# node_prototype.net
KiCad netlist of a schematic drawn in EAGLE
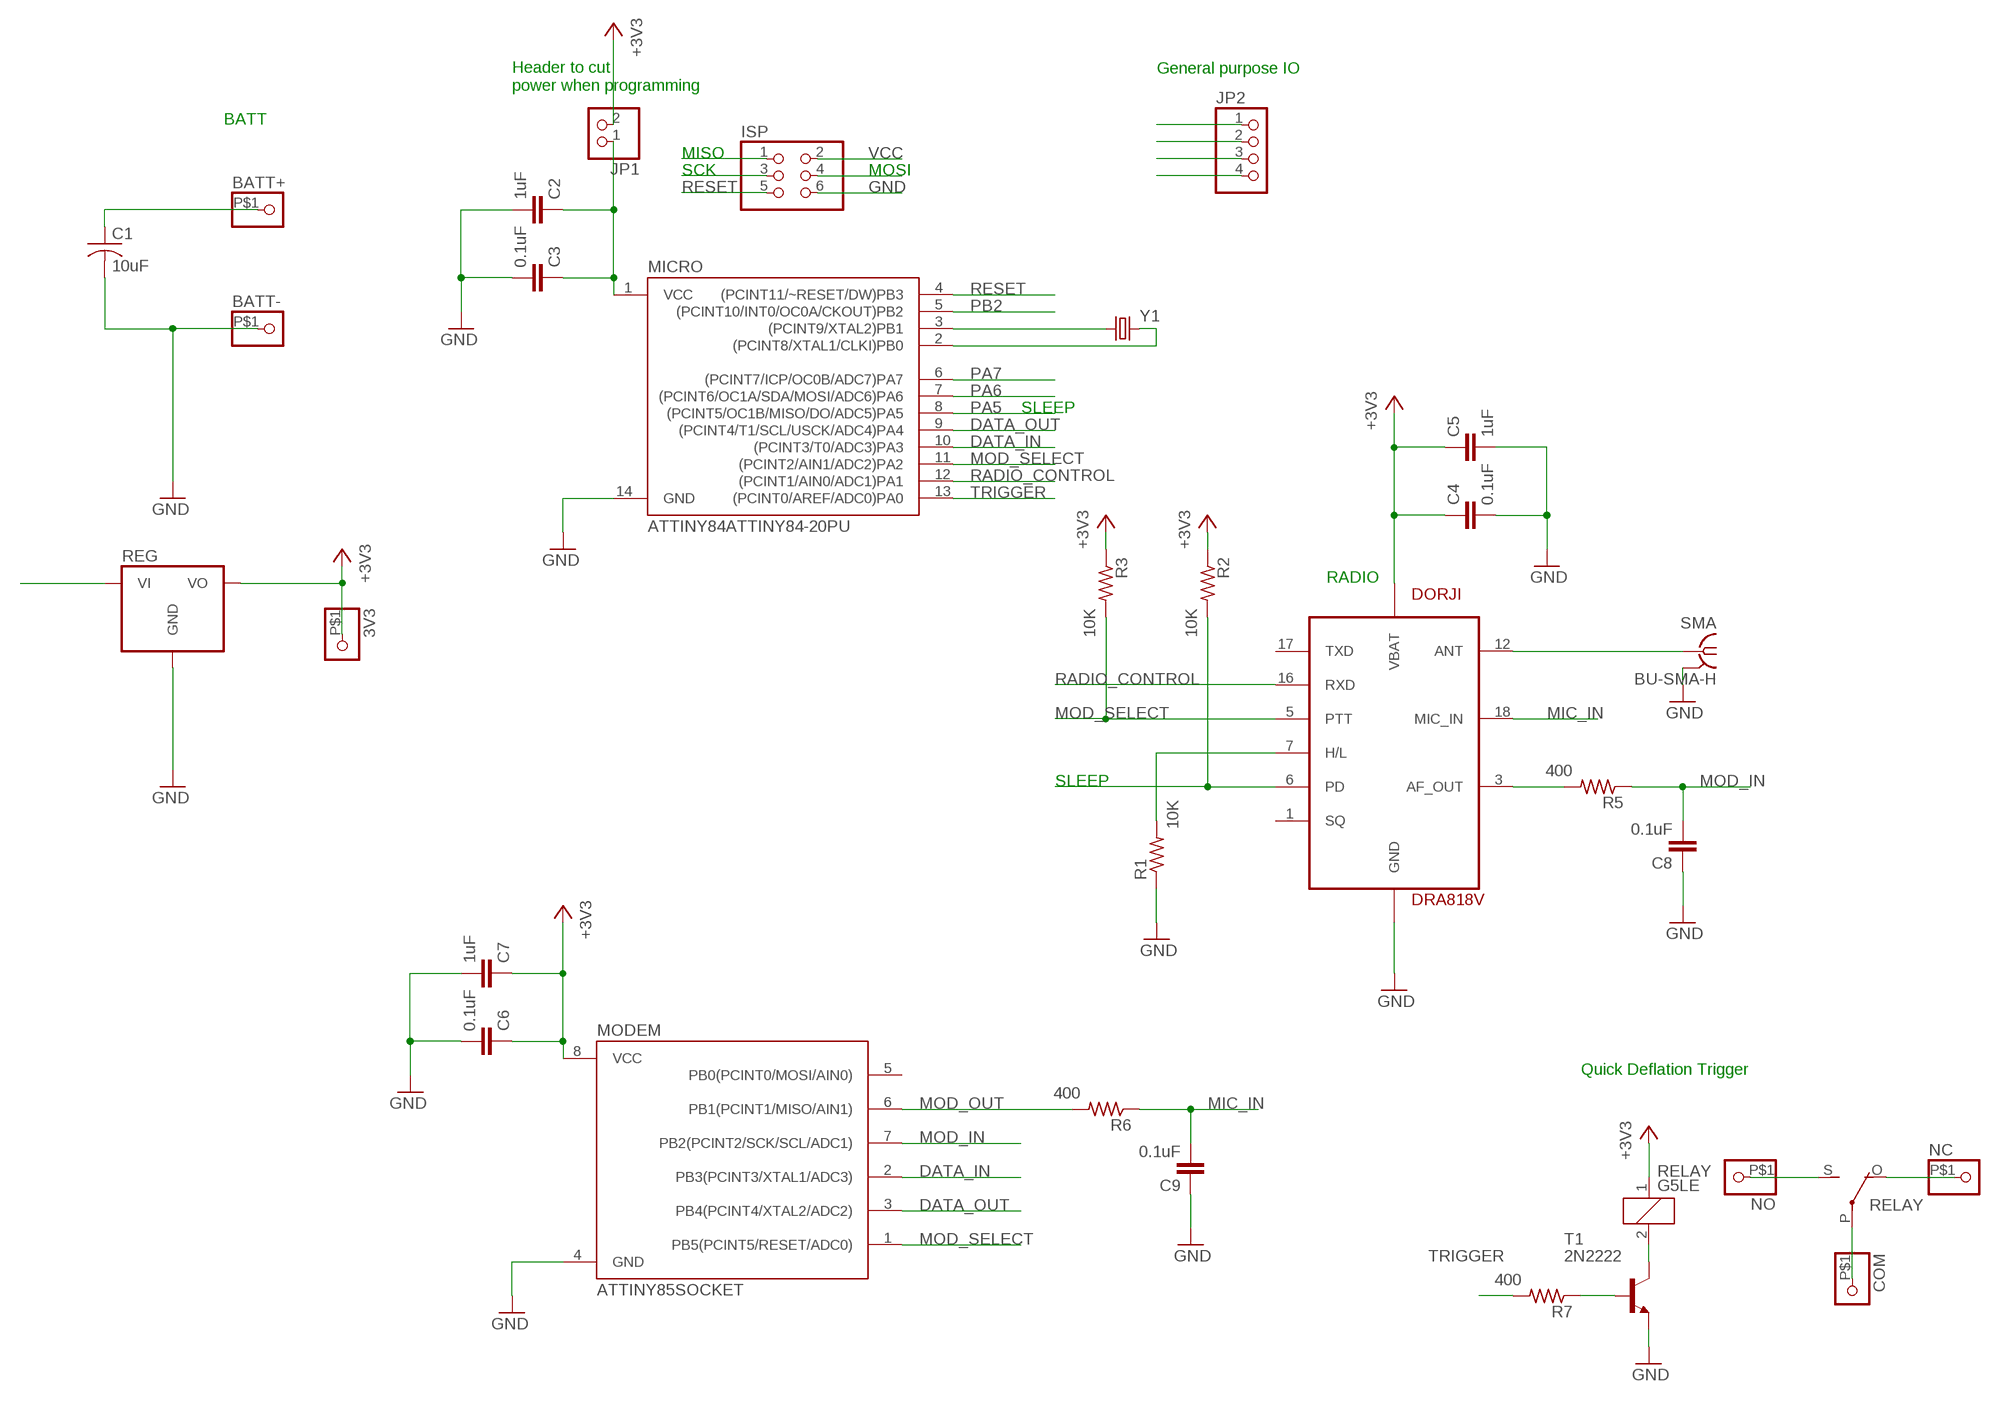
[diagram p0: schematic, sheet 1]

(export (version "E")
  (design (tool "Eeschema 10.0.6"))
  (components
    (comp (ref "3V3")
      (value "PINHD-1X1")
      (footprint "eagle-import:1X01")
      (libsource (lib "eagle-import") (part "PINHD-1X1"))
    )
    (comp (ref "BATT+")
      (value "PINHD-1X1")
      (footprint "eagle-import:1X01")
      (libsource (lib "eagle-import") (part "PINHD-1X1"))
    )
    (comp (ref "BATT-")
      (value "PINHD-1X1")
      (footprint "eagle-import:1X01")
      (libsource (lib "eagle-import") (part "PINHD-1X1"))
    )
    (comp (ref "C1")
      (value "10uF")
      (footprint "eagle-import:C025-050X050")
      (libsource (lib "eagle-import") (part "C-US025-050X050"))
    )
    (comp (ref "C2")
      (value "1uF")
      (footprint "eagle-import:C0603")
      (libsource (lib "eagle-import") (part "C-EUC0603"))
    )
    (comp (ref "C3")
      (value "0.1uF")
      (footprint "eagle-import:C0603")
      (libsource (lib "eagle-import") (part "C-EUC0603"))
    )
    (comp (ref "C4")
      (value "0.1uF")
      (footprint "eagle-import:C0603")
      (libsource (lib "eagle-import") (part "C-EUC0603"))
    )
    (comp (ref "C5")
      (value "1uF")
      (footprint "eagle-import:C0603")
      (libsource (lib "eagle-import") (part "C-EUC0603"))
    )
    (comp (ref "C6")
      (value "0.1uF")
      (footprint "eagle-import:C0603")
      (libsource (lib "eagle-import") (part "C-EUC0603"))
    )
    (comp (ref "C7")
      (value "1uF")
      (footprint "eagle-import:C0603")
      (libsource (lib "eagle-import") (part "C-EUC0603"))
    )
    (comp (ref "C8")
      (value "0.1uF")
      (footprint "eagle-import:C0603")
      (libsource (lib "eagle-import") (part "C-EUC0603"))
    )
    (comp (ref "C9")
      (value "0.1uF")
      (footprint "eagle-import:C0603")
      (libsource (lib "eagle-import") (part "C-EUC0603"))
    )
    (comp (ref "COM")
      (value "PINHD-1X1")
      (footprint "eagle-import:1X01")
      (libsource (lib "eagle-import") (part "PINHD-1X1"))
    )
    (comp (ref "DORJI")
      (value "DRA818V")
      (footprint "eagle-import:DORJI")
      (libsource (lib "eagle-import") (part "DORJIDRA818V"))
    )
    (comp (ref "ISP")
      (value "PINHD-2X3")
      (footprint "eagle-import:2X03")
      (libsource (lib "eagle-import") (part "PINHD-2X3"))
    )
    (comp (ref "JP1")
      (value "PINHD-1X2")
      (footprint "eagle-import:1X02")
      (libsource (lib "eagle-import") (part "PINHD-1X2"))
    )
    (comp (ref "JP2")
      (value "PINHD-1X4")
      (footprint "eagle-import:1X04")
      (libsource (lib "eagle-import") (part "PINHD-1X4"))
    )
    (comp (ref "MICRO")
      (value "ATTINY84ATTINY84-20PU")
      (footprint "eagle-import:DIL14")
      (libsource (lib "eagle-import") (part "ATTINY84ATTINY84-20PU"))
    )
    (comp (ref "MODEM")
      (value "ATTINY85SOCKET")
      (footprint "eagle-import:SOCKET-08")
      (libsource (lib "eagle-import") (part "ATTINY85SOCKET"))
    )
    (comp (ref "NC")
      (value "PINHD-1X1")
      (footprint "eagle-import:1X01")
      (libsource (lib "eagle-import") (part "PINHD-1X1"))
    )
    (comp (ref "NO")
      (value "PINHD-1X1")
      (footprint "eagle-import:1X01")
      (libsource (lib "eagle-import") (part "PINHD-1X1"))
    )
    (comp (ref "R1")
      (value "10K")
      (footprint "eagle-import:R0603")
      (libsource (lib "eagle-import") (part "R-US_R0603"))
    )
    (comp (ref "R2")
      (value "10K")
      (footprint "eagle-import:R0603")
      (libsource (lib "eagle-import") (part "R-US_R0603"))
    )
    (comp (ref "R3")
      (value "10K")
      (footprint "eagle-import:R0603")
      (libsource (lib "eagle-import") (part "R-US_R0603"))
    )
    (comp (ref "R5")
      (value "400")
      (footprint "eagle-import:R0603")
      (libsource (lib "eagle-import") (part "R-US_R0603"))
    )
    (comp (ref "R6")
      (value "400")
      (footprint "eagle-import:R0603")
      (libsource (lib "eagle-import") (part "R-US_R0603"))
    )
    (comp (ref "R7")
      (value "400")
      (footprint "eagle-import:R0603")
      (libsource (lib "eagle-import") (part "R-US_R0603"))
    )
    (comp (ref "REG")
      (value "AP1117-3.3SOT223")
      (footprint "eagle-import:SOT223")
      (libsource (lib "eagle-import") (part "AP1117-3.3SOT223"))
    )
    (comp (ref "RELAY")
      (value "G5LE")
      (footprint "eagle-import:G5LE")
      (libsource (lib "eagle-import") (part "G5LE"))
    )
    (comp (ref "SMA")
      (value "BU-SMA-H")
      (footprint "eagle-import:BU-SMA-H")
      (libsource (lib "eagle-import") (part "BU-SMA-H"))
    )
    (comp (ref "T1")
      (value "2N2222")
      (footprint "eagle-import:TO18")
      (libsource (lib "eagle-import") (part "2N2222"))
    )
    (comp (ref "Y1")
      (value "CRYSTAL")
      (footprint "eagle-import:MYSMD2_RESONATOR")
      (libsource (lib "eagle-import") (part "CRYSTAL"))
    )
  )
  (nets
    (net (code "1") (name "+3V3") (class "Default")
      (node (ref "3V3") (pin "P$1") (pinfunction "1_P$1") (pintype "passive"))
      (node (ref "C4") (pin "1") (pinfunction "1_1") (pintype "passive"))
      (node (ref "C5") (pin "1") (pinfunction "1_1") (pintype "passive"))
      (node (ref "C6") (pin "1") (pinfunction "1_1") (pintype "passive"))
      (node (ref "C7") (pin "1") (pinfunction "1_1") (pintype "passive"))
      (node (ref "DORJI") (pin "8") (pinfunction "VBAT_8") (pintype "bidirectional"))
      (node (ref "JP1") (pin "2") (pinfunction "2_2") (pintype "passive"))
      (node (ref "MODEM") (pin "8") (pinfunction "VCC_8") (pintype "bidirectional"))
      (node (ref "R2") (pin "1") (pinfunction "1_1") (pintype "passive"))
      (node (ref "R3") (pin "1") (pinfunction "1_1") (pintype "passive"))
      (node (ref "REG") (pin "2") (pinfunction "VO_2") (pintype "passive"))
      (node (ref "REG") (pin "4") (pinfunction "VO_4") (pintype "passive"))
      (node (ref "RELAY") (pin "1") (pinfunction "1_1") (pintype "passive"))
    )
    (net (code "2") (name "/BATT") (class "Default")
      (node (ref "BATT+") (pin "P$1") (pinfunction "1_P$1") (pintype "passive"))
      (node (ref "C1") (pin "1") (pinfunction "1_1") (pintype "passive"))
      (node (ref "REG") (pin "3") (pinfunction "VI_3") (pintype "input"))
    )
    (net (code "3") (name "/DATA_IN") (class "Default")
      (node (ref "MICRO") (pin "10") (pinfunction "(PCINT3/T0/ADC3)PA3_10") (pintype "bidirectional"))
      (node (ref "MODEM") (pin "2") (pinfunction "PB3(PCINT3/XTAL1/ADC3)_2") (pintype "bidirectional"))
    )
    (net (code "4") (name "/DATA_OUT") (class "Default")
      (node (ref "ISP") (pin "3") (pinfunction "3_3") (pintype "passive"))
      (node (ref "MICRO") (pin "9") (pinfunction "(PCINT4/T1/SCL/USCK/ADC4)PA4_9") (pintype "bidirectional"))
      (node (ref "MODEM") (pin "3") (pinfunction "PB4(PCINT4/XTAL2/ADC2)_3") (pintype "bidirectional"))
    )
    (net (code "5") (name "/MIC_IN") (class "Default")
      (node (ref "C9") (pin "2") (pinfunction "2_2") (pintype "passive"))
      (node (ref "DORJI") (pin "18") (pinfunction "MIC_IN_18") (pintype "bidirectional"))
      (node (ref "R6") (pin "1") (pinfunction "1_1") (pintype "passive"))
    )
    (net (code "6") (name "/MOD_IN") (class "Default")
      (node (ref "C8") (pin "2") (pinfunction "2_2") (pintype "passive"))
      (node (ref "MODEM") (pin "7") (pinfunction "PB2(PCINT2/SCK/SCL/ADC1)_7") (pintype "bidirectional"))
      (node (ref "R5") (pin "1") (pinfunction "1_1") (pintype "passive"))
    )
    (net (code "7") (name "/MOD_OUT") (class "Default")
      (node (ref "MODEM") (pin "6") (pinfunction "PB1(PCINT1/MISO/AIN1)_6") (pintype "bidirectional"))
      (node (ref "R6") (pin "2") (pinfunction "2_2") (pintype "passive"))
    )
    (net (code "8") (name "/MOD_SELECT") (class "Default")
      (node (ref "DORJI") (pin "5") (pinfunction "PTT_5") (pintype "bidirectional"))
      (node (ref "MICRO") (pin "11") (pinfunction "(PCINT2/AIN1/ADC2)PA2_11") (pintype "bidirectional"))
      (node (ref "MODEM") (pin "1") (pinfunction "PB5(PCINT5/RESET/ADC0)_1") (pintype "bidirectional"))
      (node (ref "R3") (pin "2") (pinfunction "2_2") (pintype "passive"))
    )
    (net (code "9") (name "/PA5") (class "Default")
      (node (ref "DORJI") (pin "6") (pinfunction "PD_6") (pintype "bidirectional"))
      (node (ref "ISP") (pin "1") (pinfunction "1_1") (pintype "passive"))
      (node (ref "JP2") (pin "4") (pinfunction "4_4") (pintype "passive"))
      (node (ref "MICRO") (pin "8") (pinfunction "(PCINT5/OC1B/MISO/DO/ADC5)PA5_8") (pintype "bidirectional"))
      (node (ref "R2") (pin "2") (pinfunction "2_2") (pintype "passive"))
    )
    (net (code "10") (name "/PA6") (class "Default")
      (node (ref "ISP") (pin "4") (pinfunction "4_4") (pintype "passive"))
      (node (ref "JP2") (pin "3") (pinfunction "3_3") (pintype "passive"))
      (node (ref "MICRO") (pin "7") (pinfunction "(PCINT6/OC1A/SDA/MOSI/ADC6)PA6_7") (pintype "bidirectional"))
    )
    (net (code "11") (name "/PA7") (class "Default")
      (node (ref "JP2") (pin "2") (pinfunction "2_2") (pintype "passive"))
      (node (ref "MICRO") (pin "6") (pinfunction "(PCINT7/ICP/OC0B/ADC7)PA7_6") (pintype "bidirectional"))
    )
    (net (code "12") (name "/PB2") (class "Default")
      (node (ref "JP2") (pin "1") (pinfunction "1_1") (pintype "passive"))
      (node (ref "MICRO") (pin "5") (pinfunction "(PCINT10/INT0/OC0A/CKOUT)PB2_5") (pintype "bidirectional"))
    )
    (net (code "13") (name "/RADIO_CONTROL") (class "Default")
      (node (ref "DORJI") (pin "16") (pinfunction "RXD_16") (pintype "bidirectional"))
      (node (ref "MICRO") (pin "12") (pinfunction "(PCINT1/AIN0/ADC1)PA1_12") (pintype "bidirectional"))
    )
    (net (code "14") (name "/RESET") (class "Default")
      (node (ref "ISP") (pin "5") (pinfunction "5_5") (pintype "passive"))
      (node (ref "MICRO") (pin "4") (pinfunction "(PCINT11/~{RESET/DW})PB3_4") (pintype "bidirectional"))
    )
    (net (code "15") (name "/TRIGGER") (class "Default")
      (node (ref "MICRO") (pin "13") (pinfunction "(PCINT0/AREF/ADC0)PA0_13") (pintype "bidirectional"))
      (node (ref "R7") (pin "2") (pinfunction "2_2") (pintype "passive"))
    )
    (net (code "16") (name "/VCC") (class "Default")
      (node (ref "C2") (pin "1") (pinfunction "1_1") (pintype "passive"))
      (node (ref "C3") (pin "1") (pinfunction "1_1") (pintype "passive"))
      (node (ref "ISP") (pin "2") (pinfunction "2_2") (pintype "passive"))
      (node (ref "JP1") (pin "1") (pinfunction "1_1") (pintype "passive"))
      (node (ref "MICRO") (pin "1") (pinfunction "VCC_1") (pintype "bidirectional"))
    )
    (net (code "17") (name "GND") (class "Default")
      (node (ref "BATT-") (pin "P$1") (pinfunction "1_P$1") (pintype "passive"))
      (node (ref "C1") (pin "2") (pinfunction "2_2") (pintype "passive"))
      (node (ref "C2") (pin "2") (pinfunction "2_2") (pintype "passive"))
      (node (ref "C3") (pin "2") (pinfunction "2_2") (pintype "passive"))
      (node (ref "C4") (pin "2") (pinfunction "2_2") (pintype "passive"))
      (node (ref "C5") (pin "2") (pinfunction "2_2") (pintype "passive"))
      (node (ref "C6") (pin "2") (pinfunction "2_2") (pintype "passive"))
      (node (ref "C7") (pin "2") (pinfunction "2_2") (pintype "passive"))
      (node (ref "C8") (pin "1") (pinfunction "1_1") (pintype "passive"))
      (node (ref "C9") (pin "1") (pinfunction "1_1") (pintype "passive"))
      (node (ref "DORJI") (pin "10") (pinfunction "GND_10") (pintype "bidirectional"))
      (node (ref "DORJI") (pin "9") (pinfunction "GND_9") (pintype "bidirectional"))
      (node (ref "ISP") (pin "6") (pinfunction "6_6") (pintype "passive"))
      (node (ref "MICRO") (pin "14") (pinfunction "GND_14") (pintype "bidirectional"))
      (node (ref "MODEM") (pin "4") (pinfunction "GND_4") (pintype "bidirectional"))
      (node (ref "R1") (pin "1") (pinfunction "1_1") (pintype "passive"))
      (node (ref "REG") (pin "1") (pinfunction "GND_1") (pintype "input"))
      (node (ref "SMA") (pin "2") (pinfunction "2_2") (pintype "passive"))
      (node (ref "SMA") (pin "3") (pinfunction "2_3") (pintype "passive"))
      (node (ref "SMA") (pin "4") (pinfunction "2_4") (pintype "passive"))
      (node (ref "SMA") (pin "5") (pinfunction "2_5") (pintype "passive"))
      (node (ref "T1") (pin "1") (pinfunction "E_1") (pintype "passive"))
    )
    (net (code "18") (name "Net-(COM-1)") (class "Default")
      (node (ref "COM") (pin "P$1") (pinfunction "1_P$1") (pintype "passive"))
      (node (ref "RELAY") (pin "P") (pinfunction "P_P") (pintype "passive"))
    )
    (net (code "19") (name "Net-(DORJI-AF_OUT)") (class "Default")
      (node (ref "DORJI") (pin "3") (pinfunction "AF_OUT_3") (pintype "bidirectional"))
      (node (ref "R5") (pin "2") (pinfunction "2_2") (pintype "passive"))
    )
    (net (code "20") (name "Net-(DORJI-ANT)") (class "Default")
      (node (ref "DORJI") (pin "12") (pinfunction "ANT_12") (pintype "bidirectional"))
      (node (ref "SMA") (pin "1") (pinfunction "1_1") (pintype "passive"))
    )
    (net (code "21") (name "Net-(DORJI-H{slash}L)") (class "Default")
      (node (ref "DORJI") (pin "7") (pinfunction "H/L_7") (pintype "bidirectional"))
      (node (ref "R1") (pin "2") (pinfunction "2_2") (pintype "passive"))
    )
    (net (code "22") (name "Net-(MICRO-(PCINT8{slash}XTAL1{slash}CLKI)PB0)") (class "Default")
      (node (ref "MICRO") (pin "2") (pinfunction "(PCINT8/XTAL1/CLKI)PB0_2") (pintype "bidirectional"))
      (node (ref "Y1") (pin "3") (pinfunction "2_3") (pintype "passive"))
    )
    (net (code "23") (name "Net-(MICRO-(PCINT9{slash}XTAL2)PB1)") (class "Default")
      (node (ref "MICRO") (pin "3") (pinfunction "(PCINT9/XTAL2)PB1_3") (pintype "bidirectional"))
      (node (ref "Y1") (pin "1") (pinfunction "1_1") (pintype "passive"))
    )
    (net (code "24") (name "Net-(NC-1)") (class "Default")
      (node (ref "NC") (pin "P$1") (pinfunction "1_P$1") (pintype "passive"))
      (node (ref "RELAY") (pin "O") (pinfunction "O_O") (pintype "passive"))
    )
    (net (code "25") (name "Net-(NO-1)") (class "Default")
      (node (ref "NO") (pin "P$1") (pinfunction "1_P$1") (pintype "passive"))
      (node (ref "RELAY") (pin "S") (pinfunction "S_S") (pintype "passive"))
    )
    (net (code "26") (name "Net-(T1-B)") (class "Default")
      (node (ref "R7") (pin "1") (pinfunction "1_1") (pintype "passive"))
      (node (ref "T1") (pin "2") (pinfunction "B_2") (pintype "passive"))
    )
    (net (code "27") (name "Net-(T1-C)") (class "Default")
      (node (ref "RELAY") (pin "2") (pinfunction "2_2") (pintype "passive"))
      (node (ref "T1") (pin "3") (pinfunction "C_3") (pintype "passive"))
    )
    (net (code "28") (name "unconnected-(DORJI-SQ-Pad1)") (class "Default")
      (node (ref "DORJI") (pin "1") (pinfunction "SQ_1") (pintype "bidirectional"))
    )
    (net (code "29") (name "unconnected-(DORJI-TXD-Pad17)") (class "Default")
      (node (ref "DORJI") (pin "17") (pinfunction "TXD_17") (pintype "bidirectional"))
    )
    (net (code "30") (name "unconnected-(MODEM-PB0(PCINT0{slash}MOSI{slash}AIN0)-Pad5)") (class "Default")
      (node (ref "MODEM") (pin "5") (pinfunction "PB0(PCINT0/MOSI/AIN0)_5") (pintype "bidirectional"))
    )
  )
)
